# Comp_PDU.net
KiCad netlist of a schematic drawn in EAGLE
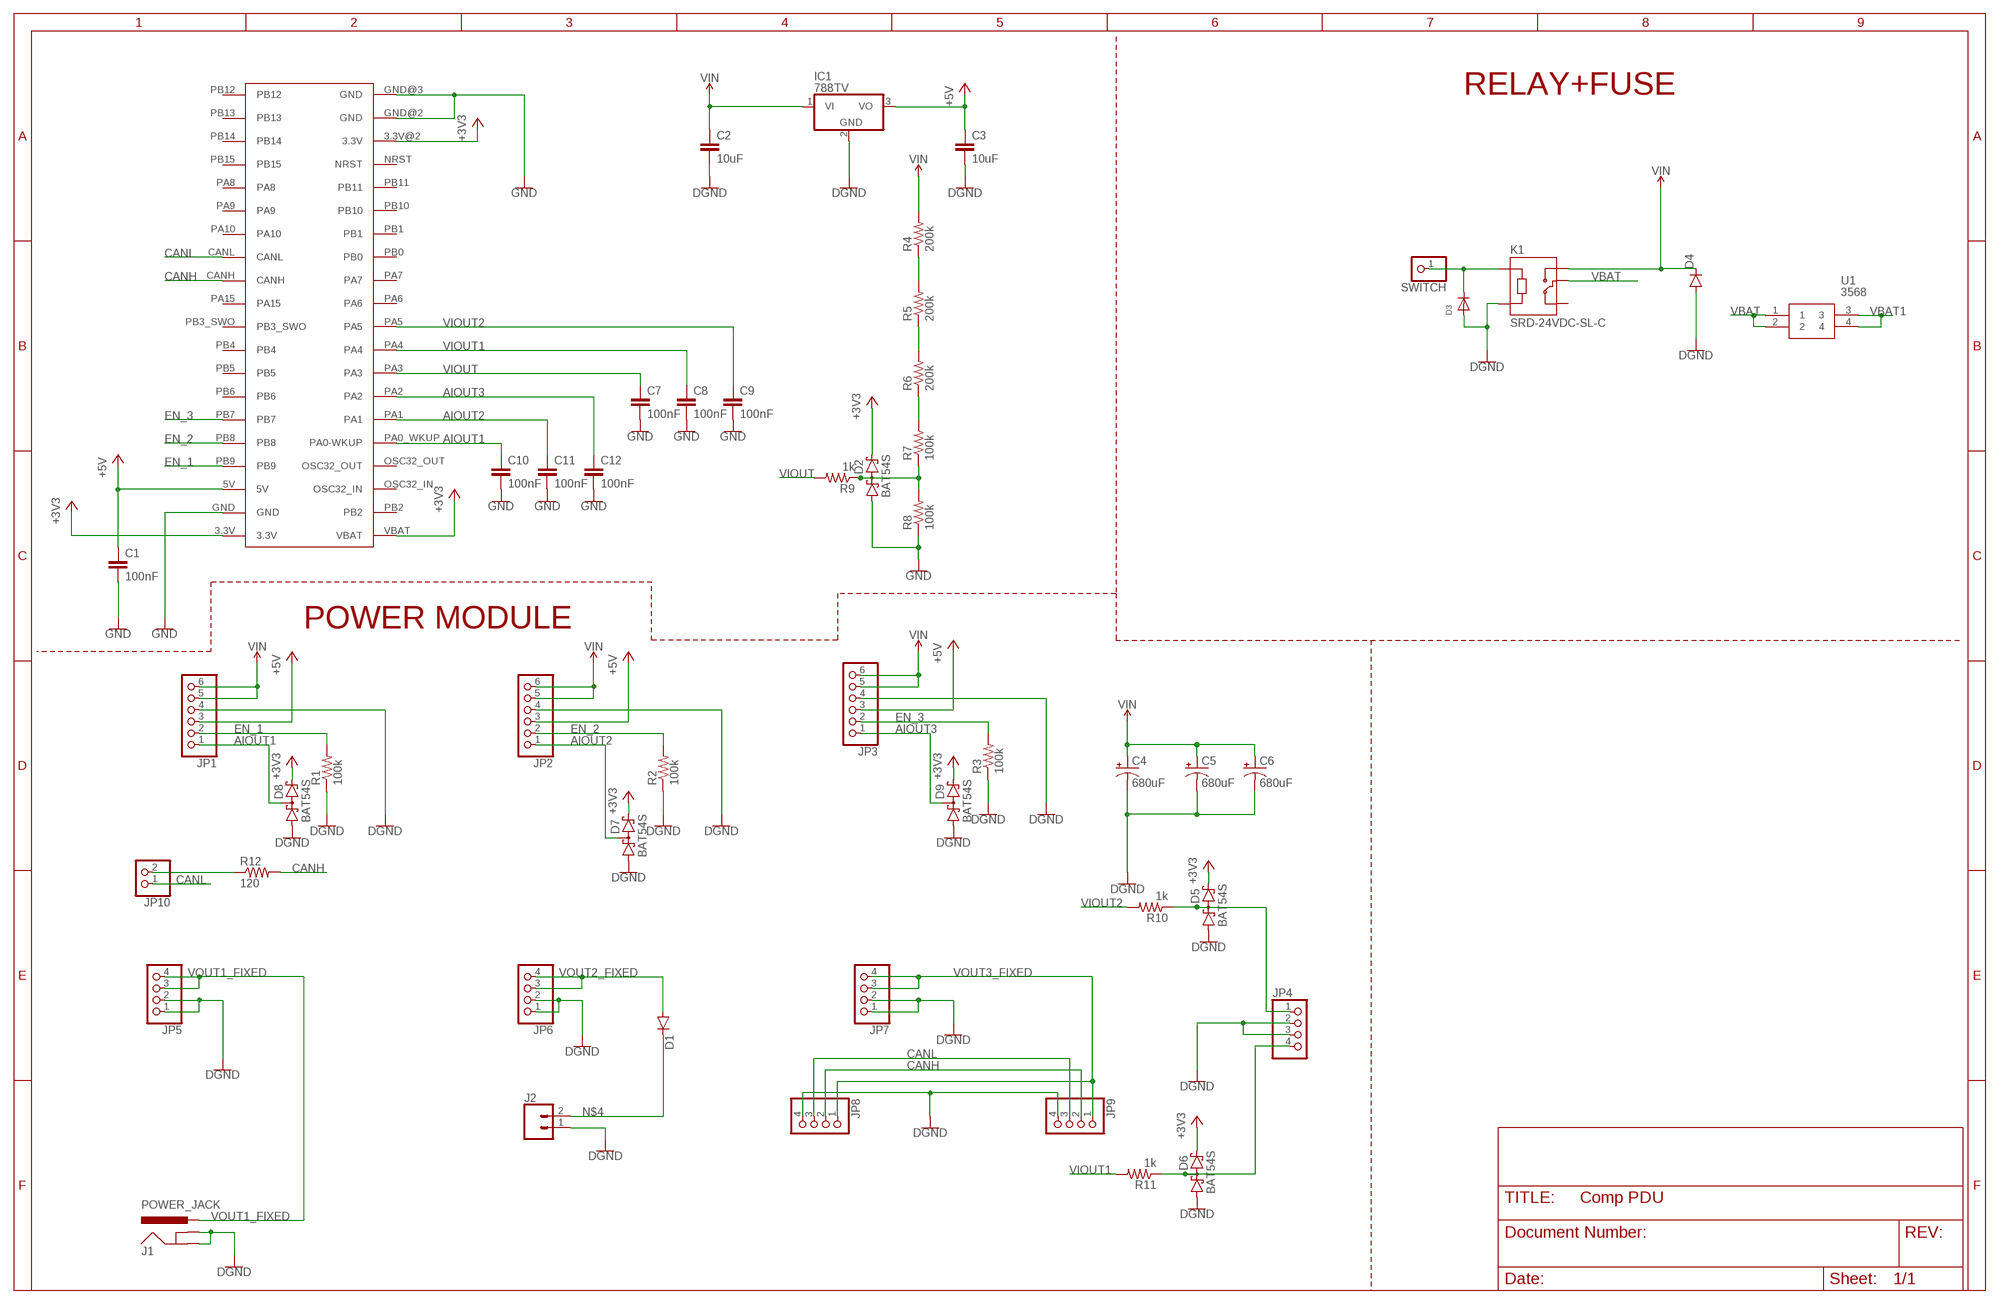
[diagram p0: schematic, sheet 1]

(export (version "E")
  (design (tool "Eeschema 10.0.6"))
  (components
    (comp (ref "C1")
      (value "100nF")
      (footprint "eagle-import:C0805")
      (libsource (lib "eagle-import") (part "C-EUC0805"))
    )
    (comp (ref "C2")
      (value "10uF")
      (footprint "eagle-import:C1206")
      (libsource (lib "eagle-import") (part "C-EUC1206"))
    )
    (comp (ref "C3")
      (value "10uF")
      (footprint "eagle-import:C1206")
      (libsource (lib "eagle-import") (part "C-EUC1206"))
    )
    (comp (ref "C4")
      (value "680uF")
      (footprint "eagle-import:E5-10,5")
      (libsource (lib "eagle-import") (part "CPOL-USE5-10.5"))
    )
    (comp (ref "C5")
      (value "680uF")
      (footprint "eagle-import:E5-10,5")
      (libsource (lib "eagle-import") (part "CPOL-USE5-10.5"))
    )
    (comp (ref "C6")
      (value "680uF")
      (footprint "eagle-import:E5-10,5")
      (libsource (lib "eagle-import") (part "CPOL-USE5-10.5"))
    )
    (comp (ref "C7")
      (value "100nF")
      (footprint "eagle-import:C0805")
      (libsource (lib "eagle-import") (part "C-EUC0805"))
    )
    (comp (ref "C8")
      (value "100nF")
      (footprint "eagle-import:C0805")
      (libsource (lib "eagle-import") (part "C-EUC0805"))
    )
    (comp (ref "C9")
      (value "100nF")
      (footprint "eagle-import:C0805")
      (libsource (lib "eagle-import") (part "C-EUC0805"))
    )
    (comp (ref "C10")
      (value "100nF")
      (footprint "eagle-import:C0805")
      (libsource (lib "eagle-import") (part "C-EUC0805"))
    )
    (comp (ref "C11")
      (value "100nF")
      (footprint "eagle-import:C0805")
      (libsource (lib "eagle-import") (part "C-EUC0805"))
    )
    (comp (ref "C12")
      (value "100nF")
      (footprint "eagle-import:C0805")
      (libsource (lib "eagle-import") (part "C-EUC0805"))
    )
    (comp (ref "D1")
      (value "DIODE-DO214AA")
      (footprint "eagle-import:DO214AA")
      (libsource (lib "eagle-import") (part "DIODE-DO214AA"))
    )
    (comp (ref "D2")
      (value "BAT54S")
      (footprint "eagle-import:SOT23")
      (libsource (lib "eagle-import") (part "BAT54S"))
    )
    (comp (ref "D3")
      (value "DIODEDO-1N4148")
      (footprint "eagle-import:DO-1N4148")
      (libsource (lib "eagle-import") (part "DIODEDO-1N4148"))
    )
    (comp (ref "D4")
      (value "DIODE-DO-214AC")
      (footprint "eagle-import:DO-214AC")
      (libsource (lib "eagle-import") (part "DIODE-DO-214AC"))
    )
    (comp (ref "D5")
      (value "BAT54S")
      (footprint "eagle-import:SOT23")
      (libsource (lib "eagle-import") (part "BAT54S"))
    )
    (comp (ref "D6")
      (value "BAT54S")
      (footprint "eagle-import:SOT23")
      (libsource (lib "eagle-import") (part "BAT54S"))
    )
    (comp (ref "D7")
      (value "BAT54S")
      (footprint "eagle-import:SOT23")
      (libsource (lib "eagle-import") (part "BAT54S"))
    )
    (comp (ref "D8")
      (value "BAT54S")
      (footprint "eagle-import:SOT23")
      (libsource (lib "eagle-import") (part "BAT54S"))
    )
    (comp (ref "D9")
      (value "BAT54S")
      (footprint "eagle-import:SOT23")
      (libsource (lib "eagle-import") (part "BAT54S"))
    )
    (comp (ref "IC1")
      (value "788TV")
      (footprint "eagle-import:TO220V")
      (libsource (lib "eagle-import") (part "78TV8"))
    )
    (comp (ref "J1")
      (value "POWER_JACK")
      (footprint "eagle-import:POWER_JACK_PTH")
      (libsource (lib "eagle-import") (part "POWER_JACK"))
    )
    (comp (ref "J2")
      (value "CONN_025MM")
      (footprint "eagle-import:SCREWTERMINAL-5MM-2")
      (libsource (lib "eagle-import") (part "CONN_025MM"))
    )
    (comp (ref "JP1")
      (value "PINHD-1X6")
      (footprint "eagle-import:1X06")
      (libsource (lib "eagle-import") (part "PINHD-1X6"))
    )
    (comp (ref "JP2")
      (value "PINHD-1X6")
      (footprint "eagle-import:1X06")
      (libsource (lib "eagle-import") (part "PINHD-1X6"))
    )
    (comp (ref "JP3")
      (value "PINHD-1X6")
      (footprint "eagle-import:1X06")
      (libsource (lib "eagle-import") (part "PINHD-1X6"))
    )
    (comp (ref "JP4")
      (value "PINHD-1X4")
      (footprint "eagle-import:1X04")
      (libsource (lib "eagle-import") (part "PINHD-1X4"))
    )
    (comp (ref "JP5")
      (value "PINHD-1X4")
      (footprint "eagle-import:1X04")
      (libsource (lib "eagle-import") (part "PINHD-1X4"))
    )
    (comp (ref "JP6")
      (value "PINHD-1X4")
      (footprint "eagle-import:1X04")
      (libsource (lib "eagle-import") (part "PINHD-1X4"))
    )
    (comp (ref "JP7")
      (value "PINHD-1X4")
      (footprint "eagle-import:1X04")
      (libsource (lib "eagle-import") (part "PINHD-1X4"))
    )
    (comp (ref "JP8")
      (value "PINHD-1X4")
      (footprint "eagle-import:1X04")
      (libsource (lib "eagle-import") (part "PINHD-1X4"))
    )
    (comp (ref "JP9")
      (value "PINHD-1X4")
      (footprint "eagle-import:1X04")
      (libsource (lib "eagle-import") (part "PINHD-1X4"))
    )
    (comp (ref "JP10")
      (value "PINHD-1X2")
      (footprint "eagle-import:1X02")
      (libsource (lib "eagle-import") (part "PINHD-1X2"))
    )
    (comp (ref "K1")
      (value "SRD-24VDC-SL-C")
      (footprint "eagle-import:RELAY_SRD-05VDC-SL-C")
      (fields (field (name "MF") "Songle Relay") (field (name "MP") "SRD-05VDC-SL-C"))
      (libsource (lib "eagle-import") (part "SRD-05VDC-SL-C"))
    )
    (comp (ref "R1")
      (value "100k")
      (footprint "eagle-import:R0805")
      (libsource (lib "eagle-import") (part "R-US_R0805"))
    )
    (comp (ref "R2")
      (value "100k")
      (footprint "eagle-import:R0805")
      (libsource (lib "eagle-import") (part "R-US_R0805"))
    )
    (comp (ref "R3")
      (value "100k")
      (footprint "eagle-import:R0805")
      (libsource (lib "eagle-import") (part "R-US_R0805"))
    )
    (comp (ref "R4")
      (value "200k")
      (footprint "eagle-import:R0805")
      (libsource (lib "eagle-import") (part "R-US_R0805"))
    )
    (comp (ref "R5")
      (value "200k")
      (footprint "eagle-import:R0805")
      (libsource (lib "eagle-import") (part "R-US_R0805"))
    )
    (comp (ref "R6")
      (value "200k")
      (footprint "eagle-import:R0805")
      (libsource (lib "eagle-import") (part "R-US_R0805"))
    )
    (comp (ref "R7")
      (value "100k")
      (footprint "eagle-import:R0805")
      (libsource (lib "eagle-import") (part "R-US_R0805"))
    )
    (comp (ref "R8")
      (value "100k")
      (footprint "eagle-import:R0805")
      (libsource (lib "eagle-import") (part "R-US_R0805"))
    )
    (comp (ref "R9")
      (value "1k")
      (footprint "eagle-import:R0805")
      (libsource (lib "eagle-import") (part "R-US_R0805"))
    )
    (comp (ref "R10")
      (value "1k")
      (footprint "eagle-import:R0805")
      (libsource (lib "eagle-import") (part "R-US_R0805"))
    )
    (comp (ref "R11")
      (value "1k")
      (footprint "eagle-import:R0805")
      (libsource (lib "eagle-import") (part "R-US_R0805"))
    )
    (comp (ref "R12")
      (value "120")
      (footprint "eagle-import:R0805")
      (libsource (lib "eagle-import") (part "R-US_R0805"))
    )
    (comp (ref "SWITCH")
      (value "PINHD-1X1")
      (footprint "eagle-import:1X01")
      (libsource (lib "eagle-import") (part "PINHD-1X1"))
    )
    (comp (ref "U$1")
      (value "STM-DEV-BOARD")
      (footprint "eagle-import:STM-DEV-BOARD")
      (libsource (lib "eagle-import") (part "STM-DEV-BOARD"))
    )
    (comp (ref "U1")
      (value "3568")
      (footprint "eagle-import:3568")
      (fields (field (name "MOUSER_PART_NUMBER") "534-3568"))
      (libsource (lib "eagle-import") (part "3568"))
    )
  )
  (nets
    (net (code "1") (name "+3V3") (class "Default")
      (node (ref "D2") (pin "2") (pinfunction "C2_2") (pintype "passive"))
      (node (ref "D5") (pin "2") (pinfunction "C2_2") (pintype "passive"))
      (node (ref "D6") (pin "2") (pinfunction "C2_2") (pintype "passive"))
      (node (ref "D7") (pin "2") (pinfunction "C2_2") (pintype "passive"))
      (node (ref "D8") (pin "2") (pinfunction "C2_2") (pintype "passive"))
      (node (ref "D9") (pin "2") (pinfunction "C2_2") (pintype "passive"))
      (node (ref "U$1") (pin "3.3V") (pinfunction "3.3V_3.3V") (pintype "bidirectional"))
      (node (ref "U$1") (pin "3.3V@2") (pinfunction "3.3V_3.3V@2") (pintype "bidirectional"))
      (node (ref "U$1") (pin "VBAT") (pinfunction "VBAT_VBAT") (pintype "bidirectional"))
    )
    (net (code "2") (name "+5V") (class "Default")
      (node (ref "C1") (pin "1") (pinfunction "1_1") (pintype "passive"))
      (node (ref "C3") (pin "1") (pinfunction "1_1") (pintype "passive"))
      (node (ref "IC1") (pin "3") (pinfunction "VO_3") (pintype "passive"))
      (node (ref "JP1") (pin "3") (pinfunction "3_3") (pintype "passive"))
      (node (ref "JP2") (pin "3") (pinfunction "3_3") (pintype "passive"))
      (node (ref "JP3") (pin "3") (pinfunction "3_3") (pintype "passive"))
      (node (ref "U$1") (pin "5V") (pinfunction "5V_5V") (pintype "bidirectional"))
    )
    (net (code "3") (name "/AIOUT1") (class "Default")
      (node (ref "C10") (pin "1") (pinfunction "1_1") (pintype "passive"))
      (node (ref "D8") (pin "3") (pinfunction "C1A2_3") (pintype "passive"))
      (node (ref "JP1") (pin "1") (pinfunction "1_1") (pintype "passive"))
      (node (ref "U$1") (pin "PA0_WKUP") (pinfunction "PA0-WKUP_PA0_WKUP") (pintype "bidirectional"))
    )
    (net (code "4") (name "/AIOUT2") (class "Default")
      (node (ref "C11") (pin "1") (pinfunction "1_1") (pintype "passive"))
      (node (ref "D7") (pin "3") (pinfunction "C1A2_3") (pintype "passive"))
      (node (ref "JP2") (pin "1") (pinfunction "1_1") (pintype "passive"))
      (node (ref "U$1") (pin "PA1") (pinfunction "PA1_PA1") (pintype "bidirectional"))
    )
    (net (code "5") (name "/AIOUT3") (class "Default")
      (node (ref "C12") (pin "1") (pinfunction "1_1") (pintype "passive"))
      (node (ref "D9") (pin "3") (pinfunction "C1A2_3") (pintype "passive"))
      (node (ref "JP3") (pin "1") (pinfunction "1_1") (pintype "passive"))
      (node (ref "U$1") (pin "PA2") (pinfunction "PA2_PA2") (pintype "bidirectional"))
    )
    (net (code "6") (name "/CANH") (class "Default")
      (node (ref "JP8") (pin "2") (pinfunction "2_2") (pintype "passive"))
      (node (ref "JP9") (pin "2") (pinfunction "2_2") (pintype "passive"))
      (node (ref "R12") (pin "2") (pinfunction "2_2") (pintype "passive"))
      (node (ref "U$1") (pin "CANH") (pinfunction "CANH_CANH") (pintype "bidirectional"))
    )
    (net (code "7") (name "/CANL") (class "Default")
      (node (ref "JP10") (pin "1") (pinfunction "1_1") (pintype "passive"))
      (node (ref "JP8") (pin "3") (pinfunction "3_3") (pintype "passive"))
      (node (ref "JP9") (pin "3") (pinfunction "3_3") (pintype "passive"))
      (node (ref "U$1") (pin "CANL") (pinfunction "CANL_CANL") (pintype "bidirectional"))
    )
    (net (code "8") (name "/EN_1") (class "Default")
      (node (ref "JP1") (pin "2") (pinfunction "2_2") (pintype "passive"))
      (node (ref "R1") (pin "2") (pinfunction "2_2") (pintype "passive"))
      (node (ref "U$1") (pin "PB9") (pinfunction "PB9_PB9") (pintype "bidirectional"))
    )
    (net (code "9") (name "/EN_2") (class "Default")
      (node (ref "JP2") (pin "2") (pinfunction "2_2") (pintype "passive"))
      (node (ref "R2") (pin "2") (pinfunction "2_2") (pintype "passive"))
      (node (ref "U$1") (pin "PB8") (pinfunction "PB8_PB8") (pintype "bidirectional"))
    )
    (net (code "10") (name "/EN_3") (class "Default")
      (node (ref "JP3") (pin "2") (pinfunction "2_2") (pintype "passive"))
      (node (ref "R3") (pin "2") (pinfunction "2_2") (pintype "passive"))
      (node (ref "U$1") (pin "PB7") (pinfunction "PB7_PB7") (pintype "bidirectional"))
    )
    (net (code "11") (name "/N$4") (class "Default")
      (node (ref "D1") (pin "C") (pinfunction "C_C") (pintype "passive"))
      (node (ref "J2") (pin "2") (pinfunction "2_2") (pintype "passive"))
    )
    (net (code "12") (name "/VBAT") (class "Default")
      (node (ref "K1") (pin "COM") (pinfunction "COM_COM") (pintype "passive"))
      (node (ref "U1") (pin "1") (pinfunction "1_1") (pintype "bidirectional"))
      (node (ref "U1") (pin "2") (pinfunction "2_2") (pintype "bidirectional"))
    )
    (net (code "13") (name "/VBAT1") (class "Default")
      (node (ref "U1") (pin "3") (pinfunction "3_3") (pintype "bidirectional"))
      (node (ref "U1") (pin "4") (pinfunction "4_4") (pintype "bidirectional"))
    )
    (net (code "14") (name "/VIOUT") (class "Default")
      (node (ref "C7") (pin "1") (pinfunction "1_1") (pintype "passive"))
      (node (ref "R9") (pin "2") (pinfunction "2_2") (pintype "passive"))
      (node (ref "U$1") (pin "PA3") (pinfunction "PA3_PA3") (pintype "bidirectional"))
    )
    (net (code "15") (name "/VIOUT1") (class "Default")
      (node (ref "C8") (pin "1") (pinfunction "1_1") (pintype "passive"))
      (node (ref "R11") (pin "2") (pinfunction "2_2") (pintype "passive"))
      (node (ref "U$1") (pin "PA4") (pinfunction "PA4_PA4") (pintype "bidirectional"))
    )
    (net (code "16") (name "/VIOUT2") (class "Default")
      (node (ref "C9") (pin "1") (pinfunction "1_1") (pintype "passive"))
      (node (ref "R10") (pin "2") (pinfunction "2_2") (pintype "passive"))
      (node (ref "U$1") (pin "PA5") (pinfunction "PA5_PA5") (pintype "bidirectional"))
    )
    (net (code "17") (name "/VOUT1_FIXED") (class "Default")
      (node (ref "J1") (pin "PWR") (pinfunction "PWR_PWR") (pintype "bidirectional"))
      (node (ref "JP5") (pin "3") (pinfunction "3_3") (pintype "passive"))
      (node (ref "JP5") (pin "4") (pinfunction "4_4") (pintype "passive"))
    )
    (net (code "18") (name "/VOUT2_FIXED") (class "Default")
      (node (ref "D1") (pin "A") (pinfunction "A_A") (pintype "passive"))
      (node (ref "JP6") (pin "3") (pinfunction "3_3") (pintype "passive"))
      (node (ref "JP6") (pin "4") (pinfunction "4_4") (pintype "passive"))
    )
    (net (code "19") (name "/VOUT3_FIXED") (class "Default")
      (node (ref "JP7") (pin "3") (pinfunction "3_3") (pintype "passive"))
      (node (ref "JP7") (pin "4") (pinfunction "4_4") (pintype "passive"))
      (node (ref "JP8") (pin "1") (pinfunction "1_1") (pintype "passive"))
      (node (ref "JP9") (pin "1") (pinfunction "1_1") (pintype "passive"))
    )
    (net (code "20") (name "DGND") (class "Default")
      (node (ref "C1") (pin "2") (pinfunction "2_2") (pintype "passive"))
      (node (ref "C10") (pin "2") (pinfunction "2_2") (pintype "passive"))
      (node (ref "C11") (pin "2") (pinfunction "2_2") (pintype "passive"))
      (node (ref "C12") (pin "2") (pinfunction "2_2") (pintype "passive"))
      (node (ref "C2") (pin "2") (pinfunction "2_2") (pintype "passive"))
      (node (ref "C3") (pin "2") (pinfunction "2_2") (pintype "passive"))
      (node (ref "C4") (pin "-") (pinfunction "-_-") (pintype "passive"))
      (node (ref "C5") (pin "-") (pinfunction "-_-") (pintype "passive"))
      (node (ref "C6") (pin "-") (pinfunction "-_-") (pintype "passive"))
      (node (ref "C7") (pin "2") (pinfunction "2_2") (pintype "passive"))
      (node (ref "C8") (pin "2") (pinfunction "2_2") (pintype "passive"))
      (node (ref "C9") (pin "2") (pinfunction "2_2") (pintype "passive"))
      (node (ref "D2") (pin "1") (pinfunction "A1_1") (pintype "passive"))
      (node (ref "D3") (pin "A") (pinfunction "A_A") (pintype "passive"))
      (node (ref "D4") (pin "A") (pinfunction "A_A") (pintype "passive"))
      (node (ref "D5") (pin "1") (pinfunction "A1_1") (pintype "passive"))
      (node (ref "D6") (pin "1") (pinfunction "A1_1") (pintype "passive"))
      (node (ref "D7") (pin "1") (pinfunction "A1_1") (pintype "passive"))
      (node (ref "D8") (pin "1") (pinfunction "A1_1") (pintype "passive"))
      (node (ref "D9") (pin "1") (pinfunction "A1_1") (pintype "passive"))
      (node (ref "IC1") (pin "2") (pinfunction "GND_2") (pintype "passive"))
      (node (ref "J1") (pin "GND") (pinfunction "GND_GND") (pintype "bidirectional"))
      (node (ref "J1") (pin "GNDBREAK") (pinfunction "GNDBREAK_GNDBREAK") (pintype "bidirectional"))
      (node (ref "J2") (pin "1") (pinfunction "1_1") (pintype "passive"))
      (node (ref "JP1") (pin "4") (pinfunction "4_4") (pintype "passive"))
      (node (ref "JP2") (pin "4") (pinfunction "4_4") (pintype "passive"))
      (node (ref "JP3") (pin "4") (pinfunction "4_4") (pintype "passive"))
      (node (ref "JP4") (pin "2") (pinfunction "2_2") (pintype "passive"))
      (node (ref "JP4") (pin "3") (pinfunction "3_3") (pintype "passive"))
      (node (ref "JP5") (pin "1") (pinfunction "1_1") (pintype "passive"))
      (node (ref "JP5") (pin "2") (pinfunction "2_2") (pintype "passive"))
      (node (ref "JP6") (pin "1") (pinfunction "1_1") (pintype "passive"))
      (node (ref "JP6") (pin "2") (pinfunction "2_2") (pintype "passive"))
      (node (ref "JP7") (pin "1") (pinfunction "1_1") (pintype "passive"))
      (node (ref "JP7") (pin "2") (pinfunction "2_2") (pintype "passive"))
      (node (ref "JP8") (pin "4") (pinfunction "4_4") (pintype "passive"))
      (node (ref "JP9") (pin "4") (pinfunction "4_4") (pintype "passive"))
      (node (ref "K1") (pin "A2") (pinfunction "A2_A2") (pintype "passive"))
      (node (ref "R1") (pin "1") (pinfunction "1_1") (pintype "passive"))
      (node (ref "R2") (pin "1") (pinfunction "1_1") (pintype "passive"))
      (node (ref "R3") (pin "1") (pinfunction "1_1") (pintype "passive"))
      (node (ref "R8") (pin "1") (pinfunction "1_1") (pintype "passive"))
      (node (ref "U$1") (pin "GND") (pinfunction "GND_GND") (pintype "bidirectional"))
      (node (ref "U$1") (pin "GND@2") (pinfunction "GND_GND@2") (pintype "bidirectional"))
      (node (ref "U$1") (pin "GND@3") (pinfunction "GND_GND@3") (pintype "bidirectional"))
    )
    (net (code "21") (name "Net-(D2-C1A2)") (class "Default")
      (node (ref "D2") (pin "3") (pinfunction "C1A2_3") (pintype "passive"))
      (node (ref "R7") (pin "1") (pinfunction "1_1") (pintype "passive"))
      (node (ref "R8") (pin "2") (pinfunction "2_2") (pintype "passive"))
      (node (ref "R9") (pin "1") (pinfunction "1_1") (pintype "passive"))
    )
    (net (code "22") (name "Net-(D3-PadC)") (class "Default")
      (node (ref "D3") (pin "C") (pinfunction "C_C") (pintype "passive"))
      (node (ref "K1") (pin "A1") (pinfunction "A1_A1") (pintype "passive"))
      (node (ref "SWITCH") (pin "1") (pinfunction "1_1") (pintype "passive"))
    )
    (net (code "23") (name "Net-(D5-C1A2)") (class "Default")
      (node (ref "D5") (pin "3") (pinfunction "C1A2_3") (pintype "passive"))
      (node (ref "JP4") (pin "1") (pinfunction "1_1") (pintype "passive"))
      (node (ref "R10") (pin "1") (pinfunction "1_1") (pintype "passive"))
    )
    (net (code "24") (name "Net-(D6-C1A2)") (class "Default")
      (node (ref "D6") (pin "3") (pinfunction "C1A2_3") (pintype "passive"))
      (node (ref "JP4") (pin "4") (pinfunction "4_4") (pintype "passive"))
      (node (ref "R11") (pin "1") (pinfunction "1_1") (pintype "passive"))
    )
    (net (code "25") (name "Net-(JP10-Pad2)") (class "Default")
      (node (ref "JP10") (pin "2") (pinfunction "2_2") (pintype "passive"))
      (node (ref "R12") (pin "1") (pinfunction "1_1") (pintype "passive"))
    )
    (net (code "26") (name "Net-(R4-Pad1)") (class "Default")
      (node (ref "R4") (pin "1") (pinfunction "1_1") (pintype "passive"))
      (node (ref "R5") (pin "2") (pinfunction "2_2") (pintype "passive"))
    )
    (net (code "27") (name "Net-(R5-Pad1)") (class "Default")
      (node (ref "R5") (pin "1") (pinfunction "1_1") (pintype "passive"))
      (node (ref "R6") (pin "2") (pinfunction "2_2") (pintype "passive"))
    )
    (net (code "28") (name "Net-(R6-Pad1)") (class "Default")
      (node (ref "R6") (pin "1") (pinfunction "1_1") (pintype "passive"))
      (node (ref "R7") (pin "2") (pinfunction "2_2") (pintype "passive"))
    )
    (net (code "29") (name "VIN") (class "Default")
      (node (ref "C2") (pin "1") (pinfunction "1_1") (pintype "passive"))
      (node (ref "C4") (pin "+") (pinfunction "+_+") (pintype "passive"))
      (node (ref "C5") (pin "+") (pinfunction "+_+") (pintype "passive"))
      (node (ref "C6") (pin "+") (pinfunction "+_+") (pintype "passive"))
      (node (ref "D4") (pin "C") (pinfunction "C_C") (pintype "passive"))
      (node (ref "IC1") (pin "1") (pinfunction "VI_1") (pintype "input"))
      (node (ref "JP1") (pin "5") (pinfunction "5_5") (pintype "passive"))
      (node (ref "JP1") (pin "6") (pinfunction "6_6") (pintype "passive"))
      (node (ref "JP2") (pin "5") (pinfunction "5_5") (pintype "passive"))
      (node (ref "JP2") (pin "6") (pinfunction "6_6") (pintype "passive"))
      (node (ref "JP3") (pin "5") (pinfunction "5_5") (pintype "passive"))
      (node (ref "JP3") (pin "6") (pinfunction "6_6") (pintype "passive"))
      (node (ref "K1") (pin "NO") (pinfunction "NO_NO") (pintype "passive"))
      (node (ref "R4") (pin "2") (pinfunction "2_2") (pintype "passive"))
    )
    (net (code "30") (name "unconnected-(K1-PadNC)") (class "Default")
      (node (ref "K1") (pin "NC") (pinfunction "NC_NC") (pintype "passive"))
    )
    (net (code "31") (name "unconnected-(U$1-PadNRST)") (class "Default")
      (node (ref "U$1") (pin "NRST") (pinfunction "NRST_NRST") (pintype "bidirectional"))
    )
    (net (code "32") (name "unconnected-(U$1-PadOSC32_IN)") (class "Default")
      (node (ref "U$1") (pin "OSC32_IN") (pinfunction "OSC32_IN_OSC32_IN") (pintype "bidirectional"))
    )
    (net (code "33") (name "unconnected-(U$1-PadOSC32_OUT)") (class "Default")
      (node (ref "U$1") (pin "OSC32_OUT") (pinfunction "OSC32_OUT_OSC32_OUT") (pintype "bidirectional"))
    )
    (net (code "34") (name "unconnected-(U$1-PadPA6)") (class "Default")
      (node (ref "U$1") (pin "PA6") (pinfunction "PA6_PA6") (pintype "bidirectional"))
    )
    (net (code "35") (name "unconnected-(U$1-PadPA7)") (class "Default")
      (node (ref "U$1") (pin "PA7") (pinfunction "PA7_PA7") (pintype "bidirectional"))
    )
    (net (code "36") (name "unconnected-(U$1-PadPA8)") (class "Default")
      (node (ref "U$1") (pin "PA8") (pinfunction "PA8_PA8") (pintype "bidirectional"))
    )
    (net (code "37") (name "unconnected-(U$1-PadPA9)") (class "Default")
      (node (ref "U$1") (pin "PA9") (pinfunction "PA9_PA9") (pintype "bidirectional"))
    )
    (net (code "38") (name "unconnected-(U$1-PadPA10)") (class "Default")
      (node (ref "U$1") (pin "PA10") (pinfunction "PA10_PA10") (pintype "bidirectional"))
    )
    (net (code "39") (name "unconnected-(U$1-PadPA15)") (class "Default")
      (node (ref "U$1") (pin "PA15") (pinfunction "PA15_PA15") (pintype "bidirectional"))
    )
    (net (code "40") (name "unconnected-(U$1-PadPB0)") (class "Default")
      (node (ref "U$1") (pin "PB0") (pinfunction "PB0_PB0") (pintype "bidirectional"))
    )
    (net (code "41") (name "unconnected-(U$1-PadPB1)") (class "Default")
      (node (ref "U$1") (pin "PB1") (pinfunction "PB1_PB1") (pintype "bidirectional"))
    )
    (net (code "42") (name "unconnected-(U$1-PadPB2)") (class "Default")
      (node (ref "U$1") (pin "PB2") (pinfunction "PB2_PB2") (pintype "bidirectional"))
    )
    (net (code "43") (name "unconnected-(U$1-PadPB3_SWO)") (class "Default")
      (node (ref "U$1") (pin "PB3_SWO") (pinfunction "PB3_SWO_PB3_SWO") (pintype "bidirectional"))
    )
    (net (code "44") (name "unconnected-(U$1-PadPB4)") (class "Default")
      (node (ref "U$1") (pin "PB4") (pinfunction "PB4_PB4") (pintype "bidirectional"))
    )
    (net (code "45") (name "unconnected-(U$1-PadPB5)") (class "Default")
      (node (ref "U$1") (pin "PB5") (pinfunction "PB5_PB5") (pintype "bidirectional"))
    )
    (net (code "46") (name "unconnected-(U$1-PadPB6)") (class "Default")
      (node (ref "U$1") (pin "PB6") (pinfunction "PB6_PB6") (pintype "bidirectional"))
    )
    (net (code "47") (name "unconnected-(U$1-PadPB10)") (class "Default")
      (node (ref "U$1") (pin "PB10") (pinfunction "PB10_PB10") (pintype "bidirectional"))
    )
    (net (code "48") (name "unconnected-(U$1-PadPB11)") (class "Default")
      (node (ref "U$1") (pin "PB11") (pinfunction "PB11_PB11") (pintype "bidirectional"))
    )
    (net (code "49") (name "unconnected-(U$1-PadPB12)") (class "Default")
      (node (ref "U$1") (pin "PB12") (pinfunction "PB12_PB12") (pintype "bidirectional"))
    )
    (net (code "50") (name "unconnected-(U$1-PadPB13)") (class "Default")
      (node (ref "U$1") (pin "PB13") (pinfunction "PB13_PB13") (pintype "bidirectional"))
    )
    (net (code "51") (name "unconnected-(U$1-PadPB14)") (class "Default")
      (node (ref "U$1") (pin "PB14") (pinfunction "PB14_PB14") (pintype "bidirectional"))
    )
    (net (code "52") (name "unconnected-(U$1-PadPB15)") (class "Default")
      (node (ref "U$1") (pin "PB15") (pinfunction "PB15_PB15") (pintype "bidirectional"))
    )
  )
)
